# MCB-MTS-Dragonfly-v2_1_0.net
KiCad netlist of a schematic drawn in EAGLE
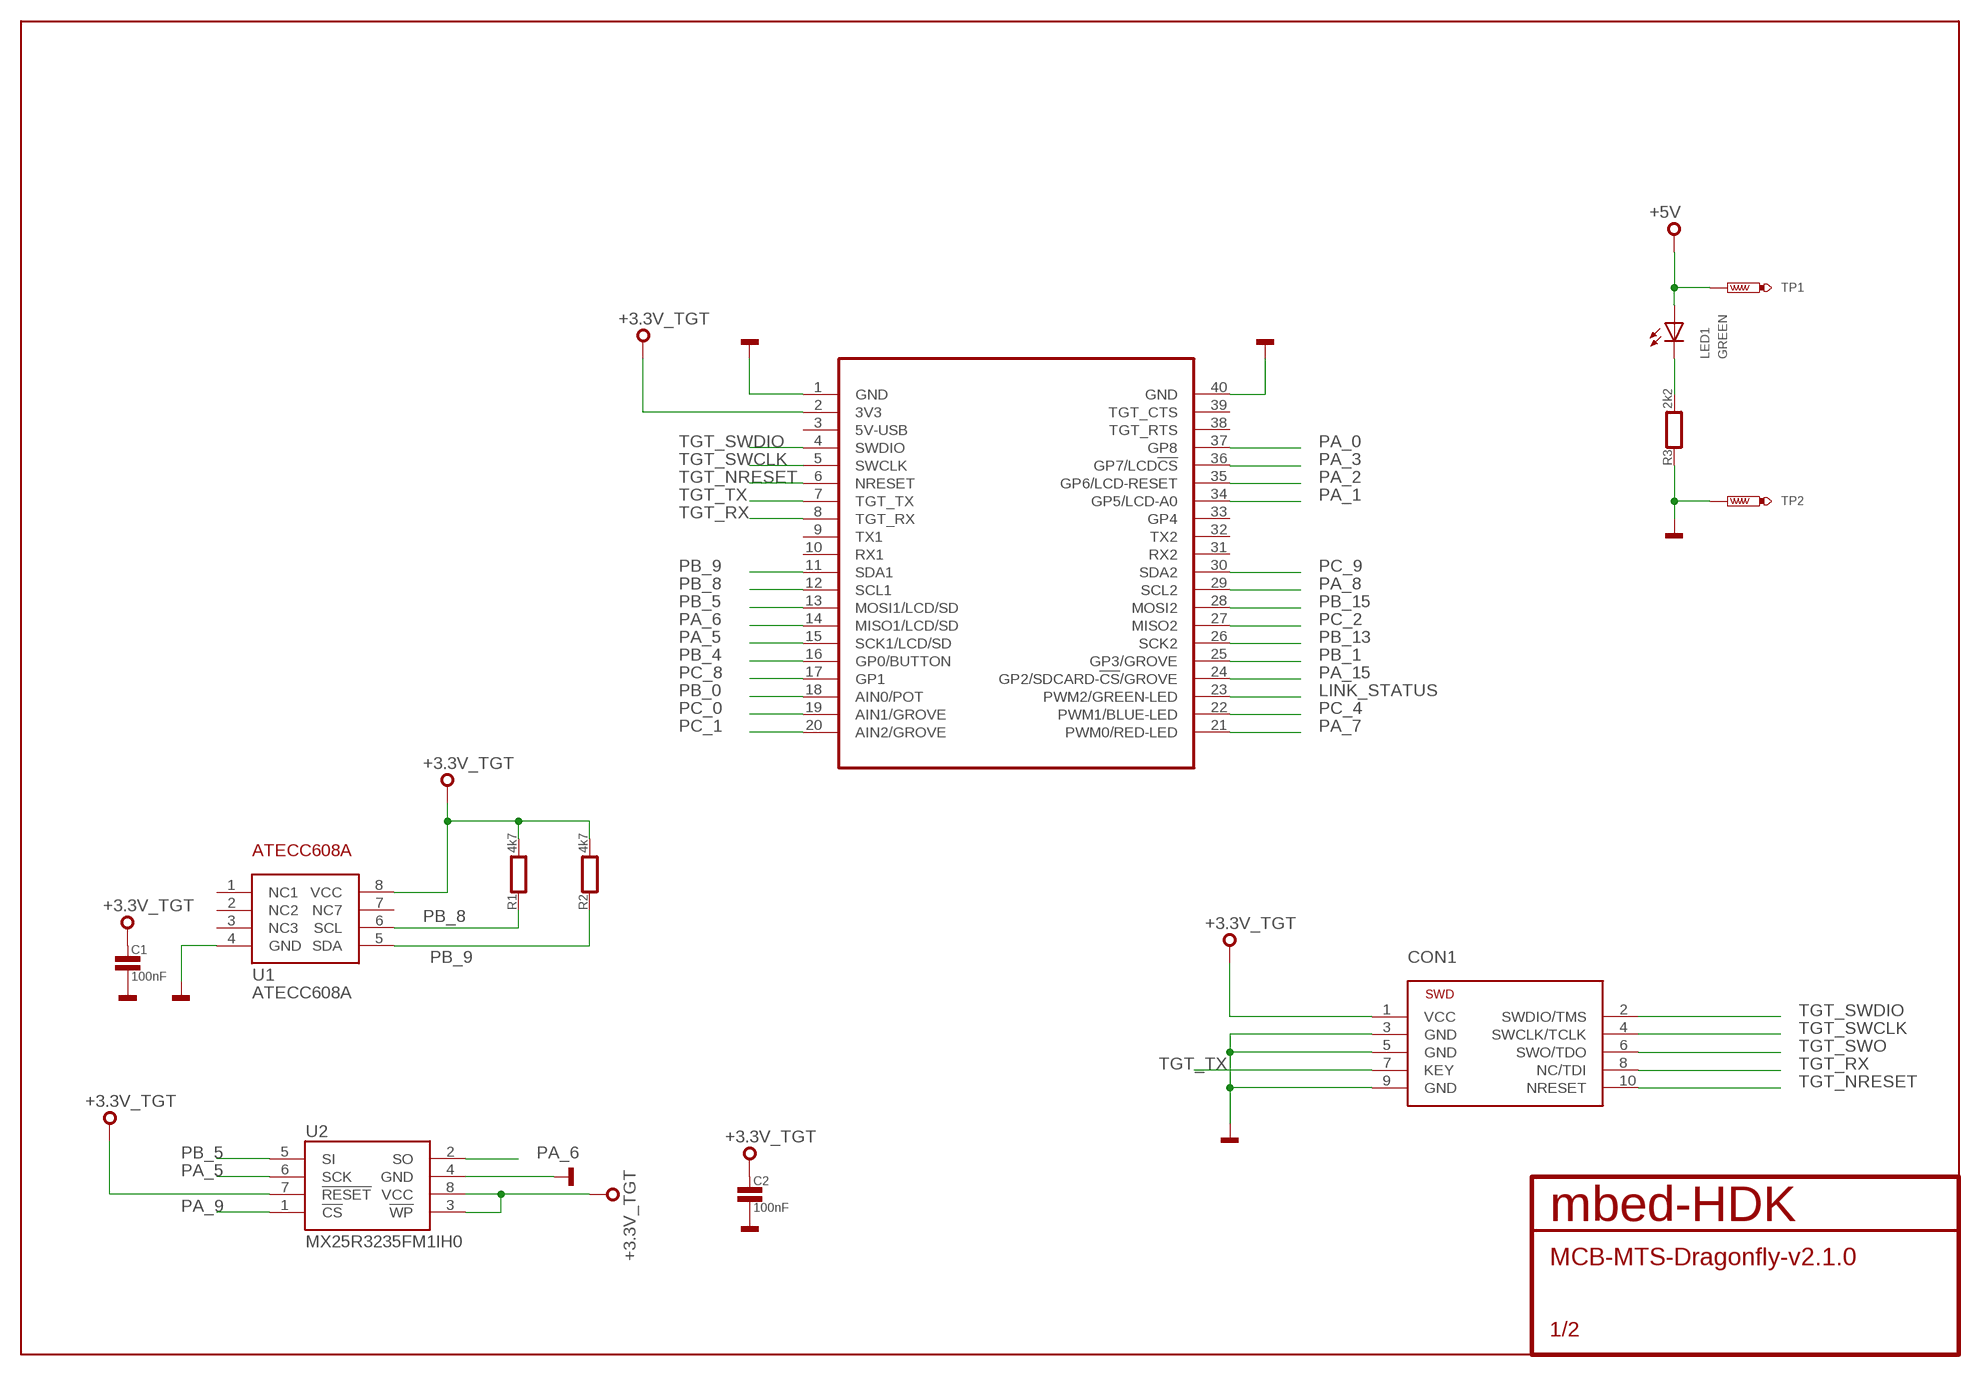
[diagram p0: schematic, sheet 1]
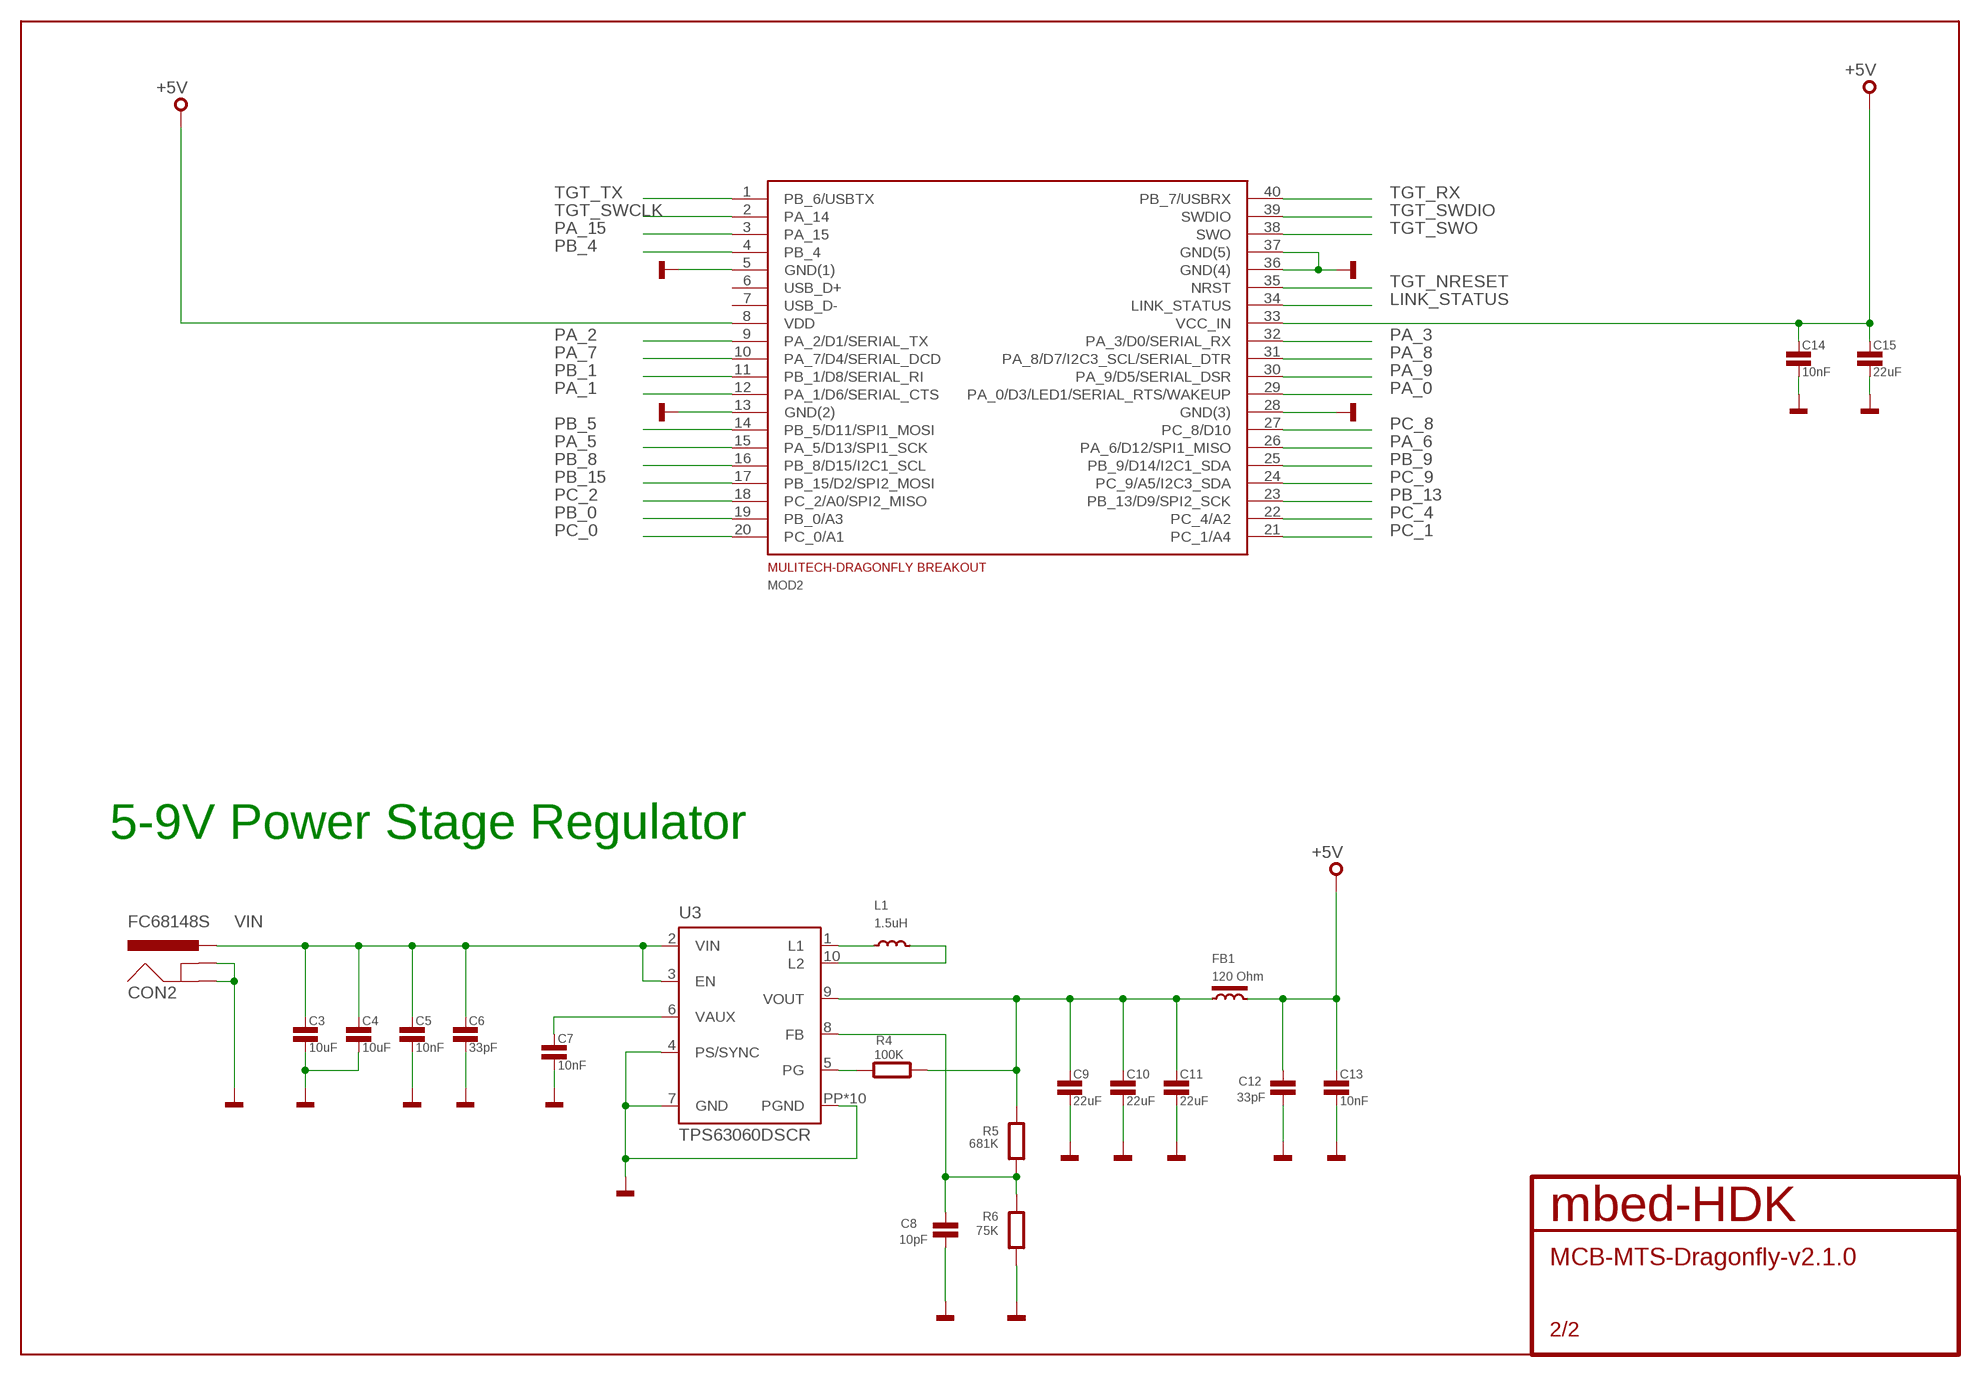
[diagram p1: schematic, sheet 2]

(export (version "E")
  (design (tool "Eeschema 10.0.6"))
  (components
    (comp (ref "C3")
      (value "10uF")
      (footprint "eagle-import:0603")
      (libsource (lib "eagle-import") (part "C0603"))
    )
    (comp (ref "C4")
      (value "10uF")
      (footprint "eagle-import:0603")
      (libsource (lib "eagle-import") (part "C0603"))
    )
    (comp (ref "C5")
      (value "10nF")
      (footprint "eagle-import:0603")
      (libsource (lib "eagle-import") (part "C0603"))
    )
    (comp (ref "C6")
      (value "33pF")
      (footprint "eagle-import:0603")
      (libsource (lib "eagle-import") (part "C0603"))
    )
    (comp (ref "C7")
      (value "10nF")
      (footprint "eagle-import:0603")
      (libsource (lib "eagle-import") (part "C0603"))
    )
    (comp (ref "C8")
      (value "10pF")
      (footprint "eagle-import:0603")
      (libsource (lib "eagle-import") (part "C0603"))
    )
    (comp (ref "C9")
      (value "22uF")
      (footprint "eagle-import:0603")
      (libsource (lib "eagle-import") (part "C0603"))
    )
    (comp (ref "C10")
      (value "22uF")
      (footprint "eagle-import:0603")
      (libsource (lib "eagle-import") (part "C0603"))
    )
    (comp (ref "C11")
      (value "22uF")
      (footprint "eagle-import:0603")
      (libsource (lib "eagle-import") (part "C0603"))
    )
    (comp (ref "C12")
      (value "33pF")
      (footprint "eagle-import:0603")
      (libsource (lib "eagle-import") (part "C0603"))
    )
    (comp (ref "C13")
      (value "10nF")
      (footprint "eagle-import:0603")
      (libsource (lib "eagle-import") (part "C0603"))
    )
    (comp (ref "C14")
      (value "10nF")
      (footprint "eagle-import:0603")
      (libsource (lib "eagle-import") (part "C0603"))
    )
    (comp (ref "C15")
      (value "22uF")
      (footprint "eagle-import:0603")
      (libsource (lib "eagle-import") (part "C0603"))
    )
    (comp (ref "CON2")
      (value "FC68148S")
      (footprint "eagle-import:FC68148S")
      (fields (field (name "MF") "Cliff"))
      (libsource (lib "eagle-import") (part "FC68148S"))
    )
    (comp (ref "FB1")
      (value "120 Ohm")
      (footprint "eagle-import:0603")
      (libsource (lib "eagle-import") (part "FB0603"))
    )
    (comp (ref "L1")
      (value "1.5uH")
      (footprint "eagle-import:XFL4020-472MEC")
      (fields (field (name "MF") "CoilCraft"))
      (libsource (lib "eagle-import") (part "INDUCTORXFL4020"))
    )
    (comp (ref "MOD2")
      (value "MULITECH-DRAGONFLY-BREAKOUT")
      (footprint "eagle-import:MULITECH-DRAGONFLY-BREAKOUT")
      (fields (field (name "MF") "Hirose"))
      (libsource (lib "eagle-import") (part "MULITECH-DRAGONFLY-BREAKOUT"))
    )
    (comp (ref "R4")
      (value "100K")
      (footprint "eagle-import:0603")
      (libsource (lib "eagle-import") (part "R0603"))
    )
    (comp (ref "R5")
      (value "681K")
      (footprint "eagle-import:0603")
      (libsource (lib "eagle-import") (part "R0603"))
    )
    (comp (ref "R6")
      (value "75K")
      (footprint "eagle-import:0603")
      (libsource (lib "eagle-import") (part "R0603"))
    )
    (comp (ref "U3")
      (value "TPS63060DSCR")
      (footprint "eagle-import:DSC-S-PWSON-N10")
      (fields (field (name "MF") "TEXAS INSTRUMENTS"))
      (libsource (lib "eagle-import") (part "TPS63060DSCR"))
    )
    (comp (ref "C1")
      (value "100nF")
      (footprint "eagle-import:0603")
      (libsource (lib "eagle-import") (part "C0603"))
    )
    (comp (ref "C2")
      (value "100nF")
      (footprint "eagle-import:0603")
      (libsource (lib "eagle-import") (part "C0603"))
    )
    (comp (ref "CON1")
      (value "SWD-10-SMD")
      (footprint "eagle-import:SWD-10-SMD")
      (libsource (lib "eagle-import") (part "SWD-10-SMD"))
    )
    (comp (ref "LED1")
      (value "GREEN")
      (footprint "eagle-import:CHIPLED_0603")
      (fields (field (name "MF") "Wurth Electronics Inc"))
      (libsource (lib "eagle-import") (part "SMD_LED0603"))
    )
    (comp (ref "MOD1")
      (value "MODULE_DAUGHTER")
      (footprint "eagle-import:MODULE_DAUGHTER")
      (libsource (lib "eagle-import") (part "MODULE_DAUGHTER"))
    )
    (comp (ref "R1")
      (value "4k7")
      (footprint "eagle-import:0603")
      (libsource (lib "eagle-import") (part "R0603"))
    )
    (comp (ref "R2")
      (value "4k7")
      (footprint "eagle-import:0603")
      (libsource (lib "eagle-import") (part "R0603"))
    )
    (comp (ref "R3")
      (value "2k2")
      (footprint "eagle-import:0603")
      (libsource (lib "eagle-import") (part "R0603"))
    )
    (comp (ref "TP1")
      (value "TEST_POINT-50R-PTH")
      (footprint "eagle-import:TP50-PTH")
      (libsource (lib "eagle-import") (part "TEST_POINT-50R-PTH"))
    )
    (comp (ref "TP2")
      (value "TEST_POINT-50R-PTH")
      (footprint "eagle-import:TP50-PTH")
      (libsource (lib "eagle-import") (part "TEST_POINT-50R-PTH"))
    )
    (comp (ref "U1")
      (value "ATECC608A")
      (footprint "eagle-import:SO8")
      (fields (field (name "MF") "Atmel"))
      (libsource (lib "eagle-import") (part "ATECC608A"))
    )
    (comp (ref "U2")
      (value "MX25R3235FM1IH0")
      (footprint "eagle-import:SO8")
      (fields (field (name "MF") "Macronix"))
      (libsource (lib "eagle-import") (part "MX25R3235FM1IH0"))
    )
  )
  (nets
    (net (code "1") (name "+3.3V_TGT") (class "Default")
      (node (ref "C1") (pin "1") (pinfunction "P$1_1") (pintype "passive"))
      (node (ref "C2") (pin "1") (pinfunction "P$1_1") (pintype "passive"))
      (node (ref "CON1") (pin "1") (pinfunction "VCC_1") (pintype "bidirectional"))
      (node (ref "MOD1") (pin "2") (pinfunction "3V3_2") (pintype "bidirectional"))
      (node (ref "R1") (pin "2") (pinfunction "P$2_2") (pintype "passive"))
      (node (ref "R2") (pin "2") (pinfunction "P$2_2") (pintype "passive"))
      (node (ref "U1") (pin "8") (pinfunction "VCC_8") (pintype "bidirectional"))
      (node (ref "U2") (pin "3") (pinfunction "~{WP}_3") (pintype "bidirectional"))
      (node (ref "U2") (pin "7") (pinfunction "~{RESET}_7") (pintype "bidirectional"))
      (node (ref "U2") (pin "8") (pinfunction "VCC_8") (pintype "bidirectional"))
    )
    (net (code "2") (name "+5V") (class "Default")
      (node (ref "C12") (pin "1") (pinfunction "P$1_1") (pintype "passive"))
      (node (ref "C13") (pin "1") (pinfunction "P$1_1") (pintype "passive"))
      (node (ref "C14") (pin "1") (pinfunction "P$1_1") (pintype "passive"))
      (node (ref "C15") (pin "1") (pinfunction "P$1_1") (pintype "passive"))
      (node (ref "FB1") (pin "2") (pinfunction "P$2_2") (pintype "bidirectional"))
      (node (ref "LED1") (pin "A") (pinfunction "A_A") (pintype "passive"))
      (node (ref "MOD2") (pin "33") (pinfunction "VCC_IN_33") (pintype "bidirectional"))
      (node (ref "MOD2") (pin "8") (pinfunction "VDD_8") (pintype "bidirectional"))
      (node (ref "TP1") (pin "TP") (pinfunction "TP_TP") (pintype "input"))
    )
    (net (code "3") (name "GND") (class "Default")
      (node (ref "C1") (pin "2") (pinfunction "P$2_2") (pintype "passive"))
      (node (ref "C10") (pin "2") (pinfunction "P$2_2") (pintype "passive"))
      (node (ref "C11") (pin "2") (pinfunction "P$2_2") (pintype "passive"))
      (node (ref "C12") (pin "2") (pinfunction "P$2_2") (pintype "passive"))
      (node (ref "C13") (pin "2") (pinfunction "P$2_2") (pintype "passive"))
      (node (ref "C14") (pin "2") (pinfunction "P$2_2") (pintype "passive"))
      (node (ref "C15") (pin "2") (pinfunction "P$2_2") (pintype "passive"))
      (node (ref "C2") (pin "2") (pinfunction "P$2_2") (pintype "passive"))
      (node (ref "C3") (pin "2") (pinfunction "P$2_2") (pintype "passive"))
      (node (ref "C4") (pin "2") (pinfunction "P$2_2") (pintype "passive"))
      (node (ref "C5") (pin "2") (pinfunction "P$2_2") (pintype "passive"))
      (node (ref "C6") (pin "2") (pinfunction "P$2_2") (pintype "passive"))
      (node (ref "C7") (pin "2") (pinfunction "P$2_2") (pintype "passive"))
      (node (ref "C8") (pin "2") (pinfunction "P$2_2") (pintype "passive"))
      (node (ref "C9") (pin "2") (pinfunction "P$2_2") (pintype "passive"))
      (node (ref "CON1") (pin "3") (pinfunction "GND_3") (pintype "bidirectional"))
      (node (ref "CON1") (pin "5") (pinfunction "GND_5") (pintype "bidirectional"))
      (node (ref "CON1") (pin "9") (pinfunction "GND_9") (pintype "bidirectional"))
      (node (ref "CON2") (pin "2") (pinfunction "GNDBREAK_2") (pintype "bidirectional"))
      (node (ref "CON2") (pin "3") (pinfunction "GND_3") (pintype "bidirectional"))
      (node (ref "MOD1") (pin "1") (pinfunction "GND_1") (pintype "bidirectional"))
      (node (ref "MOD1") (pin "40") (pinfunction "GND_40") (pintype "bidirectional"))
      (node (ref "MOD2") (pin "13") (pinfunction "GND(2)_13") (pintype "bidirectional"))
      (node (ref "MOD2") (pin "28") (pinfunction "GND(3)_28") (pintype "bidirectional"))
      (node (ref "MOD2") (pin "36") (pinfunction "GND(4)_36") (pintype "bidirectional"))
      (node (ref "MOD2") (pin "37") (pinfunction "GND(5)_37") (pintype "bidirectional"))
      (node (ref "MOD2") (pin "5") (pinfunction "GND(1)_5") (pintype "bidirectional"))
      (node (ref "R3") (pin "1") (pinfunction "P$1_1") (pintype "passive"))
      (node (ref "R6") (pin "1") (pinfunction "P$1_1") (pintype "passive"))
      (node (ref "TP2") (pin "TP") (pinfunction "TP_TP") (pintype "input"))
      (node (ref "U1") (pin "4") (pinfunction "GND_4") (pintype "bidirectional"))
      (node (ref "U2") (pin "4") (pinfunction "GND_4") (pintype "bidirectional"))
      (node (ref "U3") (pin "4") (pinfunction "PS/SYNC_4") (pintype "input"))
      (node (ref "U3") (pin "7") (pinfunction "GND_7") (pintype "input"))
      (node (ref "U3") (pin "PP") (pinfunction "PGND_PP") (pintype "power_in"))
      (node (ref "U3") (pin "PP@1") (pinfunction "PGND_PP@1") (pintype "power_in"))
      (node (ref "U3") (pin "PP@10") (pinfunction "PGND_PP@10") (pintype "power_in"))
      (node (ref "U3") (pin "PP@2") (pinfunction "PGND_PP@2") (pintype "power_in"))
      (node (ref "U3") (pin "PP@3") (pinfunction "PGND_PP@3") (pintype "power_in"))
      (node (ref "U3") (pin "PP@4") (pinfunction "PGND_PP@4") (pintype "power_in"))
      (node (ref "U3") (pin "PP@5") (pinfunction "PGND_PP@5") (pintype "power_in"))
      (node (ref "U3") (pin "PP@7") (pinfunction "PGND_PP@7") (pintype "power_in"))
      (node (ref "U3") (pin "PP@8") (pinfunction "PGND_PP@8") (pintype "power_in"))
      (node (ref "U3") (pin "PP@9") (pinfunction "PGND_PP@9") (pintype "power_in"))
    )
    (net (code "4") (name "LINK_STATUS") (class "Default")
      (node (ref "MOD1") (pin "23") (pinfunction "PWM2/GREEN-LED_23") (pintype "bidirectional"))
      (node (ref "MOD2") (pin "34") (pinfunction "LINK_STATUS_34") (pintype "bidirectional"))
    )
    (net (code "5") (name "Net-(C7-P$1)") (class "Default")
      (node (ref "C7") (pin "1") (pinfunction "P$1_1") (pintype "passive"))
      (node (ref "U3") (pin "6") (pinfunction "VAUX_6") (pintype "power_in"))
    )
    (net (code "6") (name "Net-(C8-P$1)") (class "Default")
      (node (ref "C8") (pin "1") (pinfunction "P$1_1") (pintype "passive"))
      (node (ref "R5") (pin "1") (pinfunction "P$1_1") (pintype "passive"))
      (node (ref "R6") (pin "2") (pinfunction "P$2_2") (pintype "passive"))
      (node (ref "U3") (pin "8") (pinfunction "FB_8") (pintype "input"))
    )
    (net (code "7") (name "Net-(C10-P$1)") (class "Default")
      (node (ref "C10") (pin "1") (pinfunction "P$1_1") (pintype "passive"))
      (node (ref "C11") (pin "1") (pinfunction "P$1_1") (pintype "passive"))
      (node (ref "C9") (pin "1") (pinfunction "P$1_1") (pintype "passive"))
      (node (ref "FB1") (pin "1") (pinfunction "P$1_1") (pintype "bidirectional"))
      (node (ref "R4") (pin "2") (pinfunction "P$2_2") (pintype "passive"))
      (node (ref "R5") (pin "2") (pinfunction "P$2_2") (pintype "passive"))
      (node (ref "U3") (pin "9") (pinfunction "VOUT_9") (pintype "output"))
    )
    (net (code "8") (name "Net-(R3-P$2)") (class "Default")
      (node (ref "LED1") (pin "C") (pinfunction "C_C") (pintype "passive"))
      (node (ref "R3") (pin "2") (pinfunction "P$2_2") (pintype "passive"))
    )
    (net (code "9") (name "Net-(R4-P$1)") (class "Default")
      (node (ref "R4") (pin "1") (pinfunction "P$1_1") (pintype "passive"))
      (node (ref "U3") (pin "5") (pinfunction "PG_5") (pintype "output"))
    )
    (net (code "10") (name "Net-(U3-L1)") (class "Default")
      (node (ref "L1") (pin "P$1") (pinfunction "P$1_P$1") (pintype "bidirectional"))
      (node (ref "U3") (pin "1") (pinfunction "L1_1") (pintype "input"))
    )
    (net (code "11") (name "Net-(U3-L2)") (class "Default")
      (node (ref "L1") (pin "P$2") (pinfunction "P$2_P$2") (pintype "bidirectional"))
      (node (ref "U3") (pin "10") (pinfunction "L2_10") (pintype "input"))
    )
    (net (code "12") (name "PA_0") (class "Default")
      (node (ref "MOD1") (pin "37") (pinfunction "GP8_37") (pintype "bidirectional"))
      (node (ref "MOD2") (pin "29") (pinfunction "PA_0/D3/LED1/SERIAL_RTS/WAKEUP_29") (pintype "bidirectional"))
    )
    (net (code "13") (name "PA_1") (class "Default")
      (node (ref "MOD1") (pin "34") (pinfunction "GP5/LCD-A0_34") (pintype "bidirectional"))
      (node (ref "MOD2") (pin "12") (pinfunction "PA_1/D6/SERIAL_CTS_12") (pintype "bidirectional"))
    )
    (net (code "14") (name "PA_2") (class "Default")
      (node (ref "MOD1") (pin "35") (pinfunction "GP6/LCD-RESET_35") (pintype "bidirectional"))
      (node (ref "MOD2") (pin "9") (pinfunction "PA_2/D1/SERIAL_TX_9") (pintype "bidirectional"))
    )
    (net (code "15") (name "PA_3") (class "Default")
      (node (ref "MOD1") (pin "36") (pinfunction "GP7/LCD~{CS}_36") (pintype "bidirectional"))
      (node (ref "MOD2") (pin "32") (pinfunction "PA_3/D0/SERIAL_RX_32") (pintype "bidirectional"))
    )
    (net (code "16") (name "PA_5") (class "Default")
      (node (ref "MOD1") (pin "15") (pinfunction "SCK1/LCD/SD_15") (pintype "bidirectional"))
      (node (ref "MOD2") (pin "15") (pinfunction "PA_5/D13/SPI1_SCK_15") (pintype "bidirectional"))
      (node (ref "U2") (pin "6") (pinfunction "SCK_6") (pintype "bidirectional"))
    )
    (net (code "17") (name "PA_6") (class "Default")
      (node (ref "MOD1") (pin "14") (pinfunction "MISO1/LCD/SD_14") (pintype "bidirectional"))
      (node (ref "MOD2") (pin "26") (pinfunction "PA_6/D12/SPI1_MISO_26") (pintype "bidirectional"))
      (node (ref "U2") (pin "2") (pinfunction "SO_2") (pintype "bidirectional"))
    )
    (net (code "18") (name "PA_7") (class "Default")
      (node (ref "MOD1") (pin "21") (pinfunction "PWM0/RED-LED_21") (pintype "bidirectional"))
      (node (ref "MOD2") (pin "10") (pinfunction "PA_7/D4/SERIAL_DCD_10") (pintype "bidirectional"))
    )
    (net (code "19") (name "PA_8") (class "Default")
      (node (ref "MOD1") (pin "29") (pinfunction "SCL2_29") (pintype "bidirectional"))
      (node (ref "MOD2") (pin "31") (pinfunction "PA_8/D7/I2C3_SCL/SERIAL_DTR_31") (pintype "bidirectional"))
    )
    (net (code "20") (name "PA_9") (class "Default")
      (node (ref "MOD2") (pin "30") (pinfunction "PA_9/D5/SERIAL_DSR_30") (pintype "bidirectional"))
      (node (ref "U2") (pin "1") (pinfunction "~{CS}_1") (pintype "bidirectional"))
    )
    (net (code "21") (name "PA_15") (class "Default")
      (node (ref "MOD1") (pin "24") (pinfunction "GP2/SDCARD-~{CS}/GROVE_24") (pintype "bidirectional"))
      (node (ref "MOD2") (pin "3") (pinfunction "PA_15_3") (pintype "bidirectional"))
    )
    (net (code "22") (name "PB_0") (class "Default")
      (node (ref "MOD1") (pin "18") (pinfunction "AIN0/POT_18") (pintype "bidirectional"))
      (node (ref "MOD2") (pin "19") (pinfunction "PB_0/A3_19") (pintype "bidirectional"))
    )
    (net (code "23") (name "PB_1") (class "Default")
      (node (ref "MOD1") (pin "25") (pinfunction "GP3/GROVE_25") (pintype "bidirectional"))
      (node (ref "MOD2") (pin "11") (pinfunction "PB_1/D8/SERIAL_RI_11") (pintype "bidirectional"))
    )
    (net (code "24") (name "PB_4") (class "Default")
      (node (ref "MOD1") (pin "16") (pinfunction "GP0/BUTTON_16") (pintype "bidirectional"))
      (node (ref "MOD2") (pin "4") (pinfunction "PB_4_4") (pintype "bidirectional"))
    )
    (net (code "25") (name "PB_5") (class "Default")
      (node (ref "MOD1") (pin "13") (pinfunction "MOSI1/LCD/SD_13") (pintype "bidirectional"))
      (node (ref "MOD2") (pin "14") (pinfunction "PB_5/D11/SPI1_MOSI_14") (pintype "bidirectional"))
      (node (ref "U2") (pin "5") (pinfunction "SI_5") (pintype "bidirectional"))
    )
    (net (code "26") (name "PB_8") (class "Default")
      (node (ref "MOD1") (pin "12") (pinfunction "SCL1_12") (pintype "bidirectional"))
      (node (ref "MOD2") (pin "16") (pinfunction "PB_8/D15/I2C1_SCL_16") (pintype "bidirectional"))
      (node (ref "R1") (pin "1") (pinfunction "P$1_1") (pintype "passive"))
      (node (ref "U1") (pin "6") (pinfunction "SCL_6") (pintype "bidirectional"))
    )
    (net (code "27") (name "PB_9") (class "Default")
      (node (ref "MOD1") (pin "11") (pinfunction "SDA1_11") (pintype "bidirectional"))
      (node (ref "MOD2") (pin "25") (pinfunction "PB_9/D14/I2C1_SDA_25") (pintype "bidirectional"))
      (node (ref "R2") (pin "1") (pinfunction "P$1_1") (pintype "passive"))
      (node (ref "U1") (pin "5") (pinfunction "SDA_5") (pintype "bidirectional"))
    )
    (net (code "28") (name "PB_13") (class "Default")
      (node (ref "MOD1") (pin "26") (pinfunction "SCK2_26") (pintype "bidirectional"))
      (node (ref "MOD2") (pin "23") (pinfunction "PB_13/D9/SPI2_SCK_23") (pintype "bidirectional"))
    )
    (net (code "29") (name "PB_15") (class "Default")
      (node (ref "MOD1") (pin "28") (pinfunction "MOSI2_28") (pintype "bidirectional"))
      (node (ref "MOD2") (pin "17") (pinfunction "PB_15/D2/SPI2_MOSI_17") (pintype "bidirectional"))
    )
    (net (code "30") (name "PC_0") (class "Default")
      (node (ref "MOD1") (pin "19") (pinfunction "AIN1/GROVE_19") (pintype "bidirectional"))
      (node (ref "MOD2") (pin "20") (pinfunction "PC_0/A1_20") (pintype "bidirectional"))
    )
    (net (code "31") (name "PC_1") (class "Default")
      (node (ref "MOD1") (pin "20") (pinfunction "AIN2/GROVE_20") (pintype "bidirectional"))
      (node (ref "MOD2") (pin "21") (pinfunction "PC_1/A4_21") (pintype "bidirectional"))
    )
    (net (code "32") (name "PC_2") (class "Default")
      (node (ref "MOD1") (pin "27") (pinfunction "MISO2_27") (pintype "bidirectional"))
      (node (ref "MOD2") (pin "18") (pinfunction "PC_2/A0/SPI2_MISO_18") (pintype "bidirectional"))
    )
    (net (code "33") (name "PC_4") (class "Default")
      (node (ref "MOD1") (pin "22") (pinfunction "PWM1/BLUE-LED_22") (pintype "bidirectional"))
      (node (ref "MOD2") (pin "22") (pinfunction "PC_4/A2_22") (pintype "bidirectional"))
    )
    (net (code "34") (name "PC_8") (class "Default")
      (node (ref "MOD1") (pin "17") (pinfunction "GP1_17") (pintype "bidirectional"))
      (node (ref "MOD2") (pin "27") (pinfunction "PC_8/D10_27") (pintype "bidirectional"))
    )
    (net (code "35") (name "PC_9") (class "Default")
      (node (ref "MOD1") (pin "30") (pinfunction "SDA2_30") (pintype "bidirectional"))
      (node (ref "MOD2") (pin "24") (pinfunction "PC_9/A5/I2C3_SDA_24") (pintype "bidirectional"))
    )
    (net (code "36") (name "TGT_NRESET") (class "Default")
      (node (ref "CON1") (pin "10") (pinfunction "NRESET_10") (pintype "bidirectional"))
      (node (ref "MOD1") (pin "6") (pinfunction "NRESET_6") (pintype "bidirectional"))
      (node (ref "MOD2") (pin "35") (pinfunction "NRST_35") (pintype "bidirectional"))
    )
    (net (code "37") (name "TGT_RX") (class "Default")
      (node (ref "CON1") (pin "8") (pinfunction "NC/TDI_8") (pintype "bidirectional"))
      (node (ref "MOD1") (pin "8") (pinfunction "TGT_RX_8") (pintype "bidirectional"))
      (node (ref "MOD2") (pin "40") (pinfunction "PB_7/USBRX_40") (pintype "bidirectional"))
    )
    (net (code "38") (name "TGT_SWCLK") (class "Default")
      (node (ref "CON1") (pin "4") (pinfunction "SWCLK/TCLK_4") (pintype "bidirectional"))
      (node (ref "MOD1") (pin "5") (pinfunction "SWCLK_5") (pintype "bidirectional"))
      (node (ref "MOD2") (pin "2") (pinfunction "PA_14_2") (pintype "bidirectional"))
    )
    (net (code "39") (name "TGT_SWDIO") (class "Default")
      (node (ref "CON1") (pin "2") (pinfunction "SWDIO/TMS_2") (pintype "bidirectional"))
      (node (ref "MOD1") (pin "4") (pinfunction "SWDIO_4") (pintype "bidirectional"))
      (node (ref "MOD2") (pin "39") (pinfunction "SWDIO_39") (pintype "bidirectional"))
    )
    (net (code "40") (name "TGT_SWO") (class "Default")
      (node (ref "CON1") (pin "6") (pinfunction "SWO/TDO_6") (pintype "bidirectional"))
      (node (ref "MOD2") (pin "38") (pinfunction "SWO_38") (pintype "bidirectional"))
    )
    (net (code "41") (name "TGT_TX") (class "Default")
      (node (ref "CON1") (pin "7") (pinfunction "KEY_7") (pintype "bidirectional"))
      (node (ref "MOD1") (pin "7") (pinfunction "TGT_TX_7") (pintype "bidirectional"))
      (node (ref "MOD2") (pin "1") (pinfunction "PB_6/USBTX_1") (pintype "bidirectional"))
    )
    (net (code "42") (name "VIN") (class "Default")
      (node (ref "C3") (pin "1") (pinfunction "P$1_1") (pintype "passive"))
      (node (ref "C4") (pin "1") (pinfunction "P$1_1") (pintype "passive"))
      (node (ref "C5") (pin "1") (pinfunction "P$1_1") (pintype "passive"))
      (node (ref "C6") (pin "1") (pinfunction "P$1_1") (pintype "passive"))
      (node (ref "CON2") (pin "1-1") (pinfunction "PWR_1-1") (pintype "bidirectional"))
      (node (ref "CON2") (pin "1-2") (pinfunction "PWR_1-2") (pintype "bidirectional"))
      (node (ref "U3") (pin "2") (pinfunction "VIN_2") (pintype "input"))
      (node (ref "U3") (pin "3") (pinfunction "EN_3") (pintype "input"))
    )
    (net (code "43") (name "unconnected-(MOD1-5V-USB-Pad3)") (class "Default")
      (node (ref "MOD1") (pin "3") (pinfunction "5V-USB_3") (pintype "bidirectional"))
    )
    (net (code "44") (name "unconnected-(MOD1-GP4-Pad33)") (class "Default")
      (node (ref "MOD1") (pin "33") (pinfunction "GP4_33") (pintype "bidirectional"))
    )
    (net (code "45") (name "unconnected-(MOD1-RX1-Pad10)") (class "Default")
      (node (ref "MOD1") (pin "10") (pinfunction "RX1_10") (pintype "bidirectional"))
    )
    (net (code "46") (name "unconnected-(MOD1-RX2-Pad31)") (class "Default")
      (node (ref "MOD1") (pin "31") (pinfunction "RX2_31") (pintype "bidirectional"))
    )
    (net (code "47") (name "unconnected-(MOD1-TGT_CTS-Pad39)") (class "Default")
      (node (ref "MOD1") (pin "39") (pinfunction "TGT_CTS_39") (pintype "bidirectional"))
    )
    (net (code "48") (name "unconnected-(MOD1-TGT_RTS-Pad38)") (class "Default")
      (node (ref "MOD1") (pin "38") (pinfunction "TGT_RTS_38") (pintype "bidirectional"))
    )
    (net (code "49") (name "unconnected-(MOD1-TX1-Pad9)") (class "Default")
      (node (ref "MOD1") (pin "9") (pinfunction "TX1_9") (pintype "bidirectional"))
    )
    (net (code "50") (name "unconnected-(MOD1-TX2-Pad32)") (class "Default")
      (node (ref "MOD1") (pin "32") (pinfunction "TX2_32") (pintype "bidirectional"))
    )
    (net (code "51") (name "unconnected-(MOD2-USB_D+-Pad6)") (class "Default")
      (node (ref "MOD2") (pin "6") (pinfunction "USB_D+_6") (pintype "bidirectional"))
    )
    (net (code "52") (name "unconnected-(MOD2-USB_D--Pad7)") (class "Default")
      (node (ref "MOD2") (pin "7") (pinfunction "USB_D-_7") (pintype "bidirectional"))
    )
    (net (code "53") (name "unconnected-(U1-NC1-Pad1)") (class "Default")
      (node (ref "U1") (pin "1") (pinfunction "NC1_1") (pintype "bidirectional"))
    )
    (net (code "54") (name "unconnected-(U1-NC2-Pad2)") (class "Default")
      (node (ref "U1") (pin "2") (pinfunction "NC2_2") (pintype "bidirectional"))
    )
    (net (code "55") (name "unconnected-(U1-NC3-Pad3)") (class "Default")
      (node (ref "U1") (pin "3") (pinfunction "NC3_3") (pintype "bidirectional"))
    )
    (net (code "56") (name "unconnected-(U1-NC7-Pad7)") (class "Default")
      (node (ref "U1") (pin "7") (pinfunction "NC7_7") (pintype "bidirectional"))
    )
  )
)
